# weather_baloon_RX.net
KiCad netlist of a schematic drawn in EAGLE
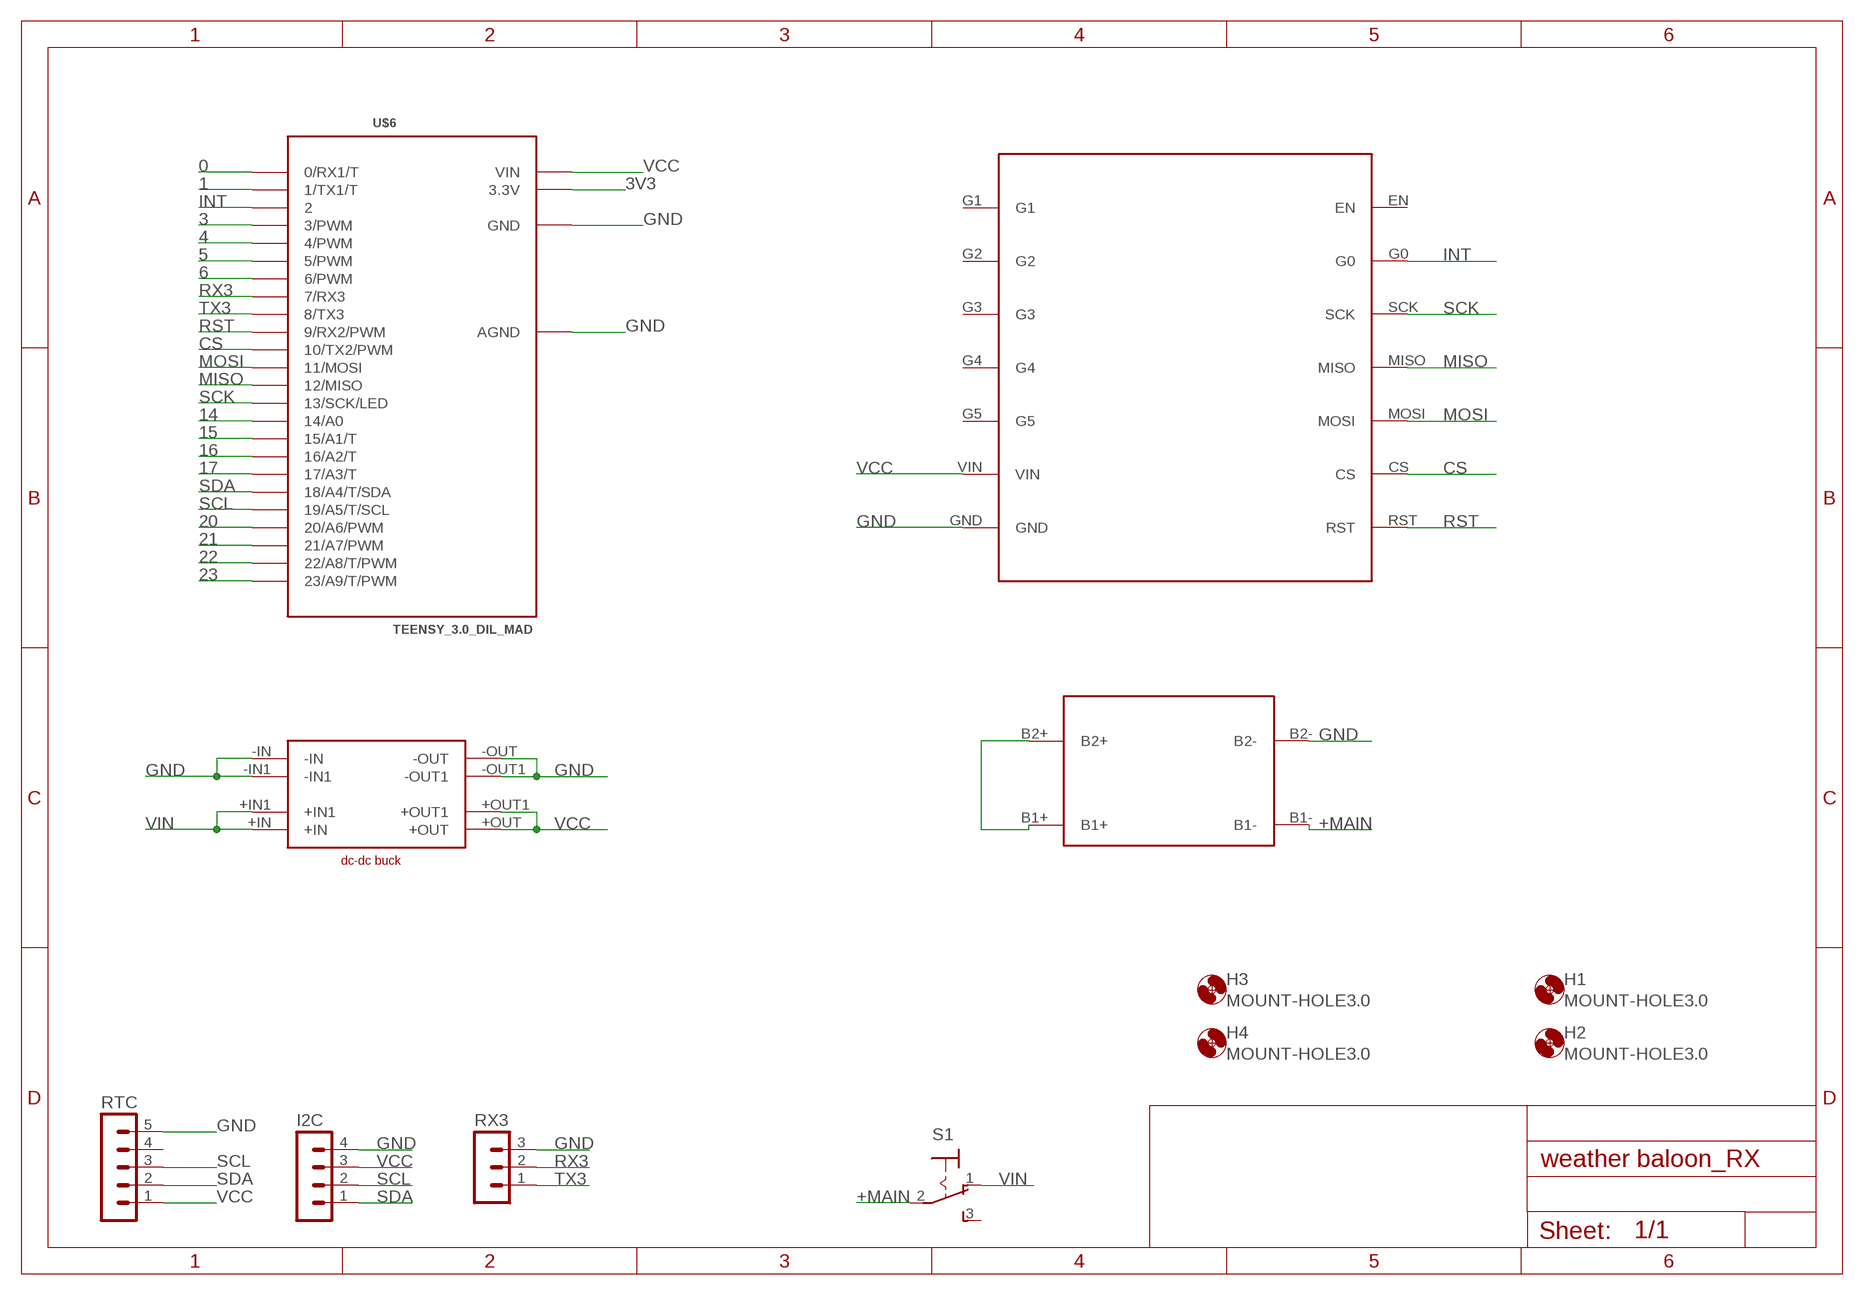
[diagram p0: schematic, sheet 1]

(export (version "E")
  (design (tool "Eeschema 10.0.6"))
  (components
    (comp (ref "H1")
      (value "MOUNT-HOLE3.0")
      (footprint "eagle-import:3,0")
      (libsource (lib "eagle-import") (part "MOUNT-HOLE3.0"))
    )
    (comp (ref "H2")
      (value "MOUNT-HOLE3.0")
      (footprint "eagle-import:3,0")
      (libsource (lib "eagle-import") (part "MOUNT-HOLE3.0"))
    )
    (comp (ref "H3")
      (value "MOUNT-HOLE3.0")
      (footprint "eagle-import:3,0")
      (libsource (lib "eagle-import") (part "MOUNT-HOLE3.0"))
    )
    (comp (ref "H4")
      (value "MOUNT-HOLE3.0")
      (footprint "eagle-import:3,0")
      (libsource (lib "eagle-import") (part "MOUNT-HOLE3.0"))
    )
    (comp (ref "I2C")
      (value "MA04-1")
      (footprint "eagle-import:MA04-1")
      (libsource (lib "eagle-import") (part "MA04-1"))
    )
    (comp (ref "RTC")
      (value "MA05-1")
      (footprint "eagle-import:MA05-1")
      (libsource (lib "eagle-import") (part "MA05-1"))
    )
    (comp (ref "RX3")
      (value "MA03-1")
      (footprint "eagle-import:MA03-1")
      (libsource (lib "eagle-import") (part "MA03-1"))
    )
    (comp (ref "S1")
      (value "320-916")
      (footprint "eagle-import:320-916")
      (libsource (lib "eagle-import") (part "320-916"))
    )
    (comp (ref "U$2")
      (value "RFM96_MAD")
      (footprint "eagle-import:RFM96")
      (libsource (lib "eagle-import") (part "RFM96_MAD"))
    )
    (comp (ref "U$3")
      (value "DC-DC_BUCK_MAD")
      (footprint "eagle-import:DC-DC_BUCK")
      (libsource (lib "eagle-import") (part "DC-DC_BUCK_MAD"))
    )
    (comp (ref "U$4")
      (value "18650-2")
      (footprint "eagle-import:18650-2")
      (libsource (lib "eagle-import") (part "18650-2"))
    )
    (comp (ref "U$6")
      (value "TEENSY_3.0_DIL_MAD")
      (footprint "eagle-import:TEENSY_3.0_DIL_MAD")
      (libsource (lib "eagle-import") (part "TEENSY_3.0_DIL_MAD"))
    )
  )
  (nets
    (net (code "1") (name "/+MAIN") (class "Default")
      (node (ref "S1") (pin "2") (pinfunction "P_2") (pintype "passive"))
      (node (ref "U$4") (pin "B1-") (pinfunction "B1-_B1-") (pintype "bidirectional"))
    )
    (net (code "2") (name "/0") (class "Default")
      (node (ref "U$6") (pin "0") (pinfunction "0/RX1/T_0") (pintype "bidirectional"))
    )
    (net (code "3") (name "/1") (class "Default")
      (node (ref "U$6") (pin "1") (pinfunction "1/TX1/T_1") (pintype "bidirectional"))
    )
    (net (code "4") (name "/3") (class "Default")
      (node (ref "U$6") (pin "3") (pinfunction "3/PWM_3") (pintype "bidirectional"))
    )
    (net (code "5") (name "/3V3") (class "Default")
      (node (ref "U$6") (pin "3.3V") (pinfunction "3.3V_3.3V") (pintype "power_in"))
    )
    (net (code "6") (name "/4") (class "Default")
      (node (ref "U$6") (pin "4") (pinfunction "4/PWM_4") (pintype "bidirectional"))
    )
    (net (code "7") (name "/5") (class "Default")
      (node (ref "U$6") (pin "5") (pinfunction "5/PWM_5") (pintype "bidirectional"))
    )
    (net (code "8") (name "/6") (class "Default")
      (node (ref "U$6") (pin "6") (pinfunction "6/PWM_6") (pintype "bidirectional"))
    )
    (net (code "9") (name "/14") (class "Default")
      (node (ref "U$6") (pin "14/A0") (pinfunction "14/A0_14/A0") (pintype "bidirectional"))
    )
    (net (code "10") (name "/15") (class "Default")
      (node (ref "U$6") (pin "15/A1") (pinfunction "15/A1/T_15/A1") (pintype "bidirectional"))
    )
    (net (code "11") (name "/16") (class "Default")
      (node (ref "U$6") (pin "16/A2") (pinfunction "16/A2/T_16/A2") (pintype "bidirectional"))
    )
    (net (code "12") (name "/17") (class "Default")
      (node (ref "U$6") (pin "17/A3") (pinfunction "17/A3/T_17/A3") (pintype "bidirectional"))
    )
    (net (code "13") (name "/20") (class "Default")
      (node (ref "U$6") (pin "20/A6") (pinfunction "20/A6/PWM_20/A6") (pintype "bidirectional"))
    )
    (net (code "14") (name "/21") (class "Default")
      (node (ref "U$6") (pin "21/A7") (pinfunction "21/A7/PWM_21/A7") (pintype "bidirectional"))
    )
    (net (code "15") (name "/22") (class "Default")
      (node (ref "U$6") (pin "22/A8") (pinfunction "22/A8/T/PWM_22/A8") (pintype "bidirectional"))
    )
    (net (code "16") (name "/23") (class "Default")
      (node (ref "U$6") (pin "23/A9") (pinfunction "23/A9/T/PWM_23/A9") (pintype "bidirectional"))
    )
    (net (code "17") (name "/CS") (class "Default")
      (node (ref "U$2") (pin "CS") (pinfunction "CS_CS") (pintype "bidirectional"))
      (node (ref "U$6") (pin "10") (pinfunction "10/TX2/PWM_10") (pintype "bidirectional"))
    )
    (net (code "18") (name "/GND") (class "Default")
      (node (ref "I2C") (pin "4") (pinfunction "4_4") (pintype "passive"))
      (node (ref "RTC") (pin "5") (pinfunction "5_5") (pintype "passive"))
      (node (ref "RX3") (pin "3") (pinfunction "3_3") (pintype "passive"))
      (node (ref "U$2") (pin "GND") (pinfunction "GND_GND") (pintype "bidirectional"))
      (node (ref "U$3") (pin "-IN") (pinfunction "-IN_-IN") (pintype "bidirectional"))
      (node (ref "U$3") (pin "-IN1") (pinfunction "-IN1_-IN1") (pintype "bidirectional"))
      (node (ref "U$3") (pin "-OUT") (pinfunction "-OUT_-OUT") (pintype "bidirectional"))
      (node (ref "U$3") (pin "-OUT1") (pinfunction "-OUT1_-OUT1") (pintype "bidirectional"))
      (node (ref "U$4") (pin "B2-") (pinfunction "B2-_B2-") (pintype "bidirectional"))
      (node (ref "U$6") (pin "AGND") (pinfunction "AGND_AGND") (pintype "power_in"))
      (node (ref "U$6") (pin "GND") (pinfunction "GND_GND") (pintype "power_in"))
    )
    (net (code "19") (name "/INT") (class "Default")
      (node (ref "U$2") (pin "G0") (pinfunction "G0_G0") (pintype "bidirectional"))
      (node (ref "U$6") (pin "2") (pinfunction "2_2") (pintype "bidirectional"))
    )
    (net (code "20") (name "/MISO") (class "Default")
      (node (ref "U$2") (pin "MISO") (pinfunction "MISO_MISO") (pintype "bidirectional"))
      (node (ref "U$6") (pin "12") (pinfunction "12/MISO_12") (pintype "bidirectional"))
    )
    (net (code "21") (name "/MOSI") (class "Default")
      (node (ref "U$2") (pin "MOSI") (pinfunction "MOSI_MOSI") (pintype "bidirectional"))
      (node (ref "U$6") (pin "11") (pinfunction "11/MOSI_11") (pintype "bidirectional"))
    )
    (net (code "22") (name "/RST") (class "Default")
      (node (ref "U$2") (pin "RST") (pinfunction "RST_RST") (pintype "bidirectional"))
      (node (ref "U$6") (pin "9") (pinfunction "9/RX2/PWM_9") (pintype "bidirectional"))
    )
    (net (code "23") (name "/RX3") (class "Default")
      (node (ref "RX3") (pin "2") (pinfunction "2_2") (pintype "passive"))
      (node (ref "U$6") (pin "7") (pinfunction "7/RX3_7") (pintype "bidirectional"))
    )
    (net (code "24") (name "/SCK") (class "Default")
      (node (ref "U$2") (pin "SCK") (pinfunction "SCK_SCK") (pintype "bidirectional"))
      (node (ref "U$6") (pin "13") (pinfunction "13/SCK/LED_13") (pintype "bidirectional"))
    )
    (net (code "25") (name "/SCL") (class "Default")
      (node (ref "I2C") (pin "2") (pinfunction "2_2") (pintype "passive"))
      (node (ref "RTC") (pin "3") (pinfunction "3_3") (pintype "passive"))
      (node (ref "U$6") (pin "19/A5") (pinfunction "19/A5/T/SCL_19/A5") (pintype "bidirectional"))
    )
    (net (code "26") (name "/SDA") (class "Default")
      (node (ref "I2C") (pin "1") (pinfunction "1_1") (pintype "passive"))
      (node (ref "RTC") (pin "2") (pinfunction "2_2") (pintype "passive"))
      (node (ref "U$6") (pin "18/A4") (pinfunction "18/A4/T/SDA_18/A4") (pintype "bidirectional"))
    )
    (net (code "27") (name "/TX3") (class "Default")
      (node (ref "RX3") (pin "1") (pinfunction "1_1") (pintype "passive"))
      (node (ref "U$6") (pin "8") (pinfunction "8/TX3_8") (pintype "bidirectional"))
    )
    (net (code "28") (name "/VCC") (class "Default")
      (node (ref "I2C") (pin "3") (pinfunction "3_3") (pintype "passive"))
      (node (ref "RTC") (pin "1") (pinfunction "1_1") (pintype "passive"))
      (node (ref "U$2") (pin "VIN") (pinfunction "VIN_VIN") (pintype "bidirectional"))
      (node (ref "U$3") (pin "+OUT") (pinfunction "+OUT_+OUT") (pintype "bidirectional"))
      (node (ref "U$3") (pin "+OUT1") (pinfunction "+OUT1_+OUT1") (pintype "bidirectional"))
      (node (ref "U$6") (pin "VIN") (pinfunction "VIN_VIN") (pintype "power_in"))
    )
    (net (code "29") (name "/VIN") (class "Default")
      (node (ref "S1") (pin "1") (pinfunction "O_1") (pintype "passive"))
      (node (ref "U$3") (pin "+IN") (pinfunction "+IN_+IN") (pintype "bidirectional"))
      (node (ref "U$3") (pin "+IN1") (pinfunction "+IN1_+IN1") (pintype "bidirectional"))
    )
    (net (code "30") (name "Net-(U$4-PadB1+)") (class "Default")
      (node (ref "U$4") (pin "B1+") (pinfunction "B1+_B1+") (pintype "bidirectional"))
      (node (ref "U$4") (pin "B2+") (pinfunction "B2+_B2+") (pintype "bidirectional"))
    )
    (net (code "31") (name "unconnected-(RTC-Pad4)") (class "Default")
      (node (ref "RTC") (pin "4") (pinfunction "4_4") (pintype "passive"))
    )
    (net (code "32") (name "unconnected-(S1-S-Pad3)") (class "Default")
      (node (ref "S1") (pin "3") (pinfunction "S_3") (pintype "passive"))
    )
    (net (code "33") (name "unconnected-(U$2-PadEN)") (class "Default")
      (node (ref "U$2") (pin "EN") (pinfunction "EN_EN") (pintype "bidirectional"))
    )
    (net (code "34") (name "unconnected-(U$2-PadG1)") (class "Default")
      (node (ref "U$2") (pin "G1") (pinfunction "G1_G1") (pintype "bidirectional"))
    )
    (net (code "35") (name "unconnected-(U$2-PadG2)") (class "Default")
      (node (ref "U$2") (pin "G2") (pinfunction "G2_G2") (pintype "bidirectional"))
    )
    (net (code "36") (name "unconnected-(U$2-PadG3)") (class "Default")
      (node (ref "U$2") (pin "G3") (pinfunction "G3_G3") (pintype "bidirectional"))
    )
    (net (code "37") (name "unconnected-(U$2-PadG4)") (class "Default")
      (node (ref "U$2") (pin "G4") (pinfunction "G4_G4") (pintype "bidirectional"))
    )
    (net (code "38") (name "unconnected-(U$2-PadG5)") (class "Default")
      (node (ref "U$2") (pin "G5") (pinfunction "G5_G5") (pintype "bidirectional"))
    )
  )
)
